# soldering_analog.net
KiCad netlist of a schematic drawn in Altium Designer
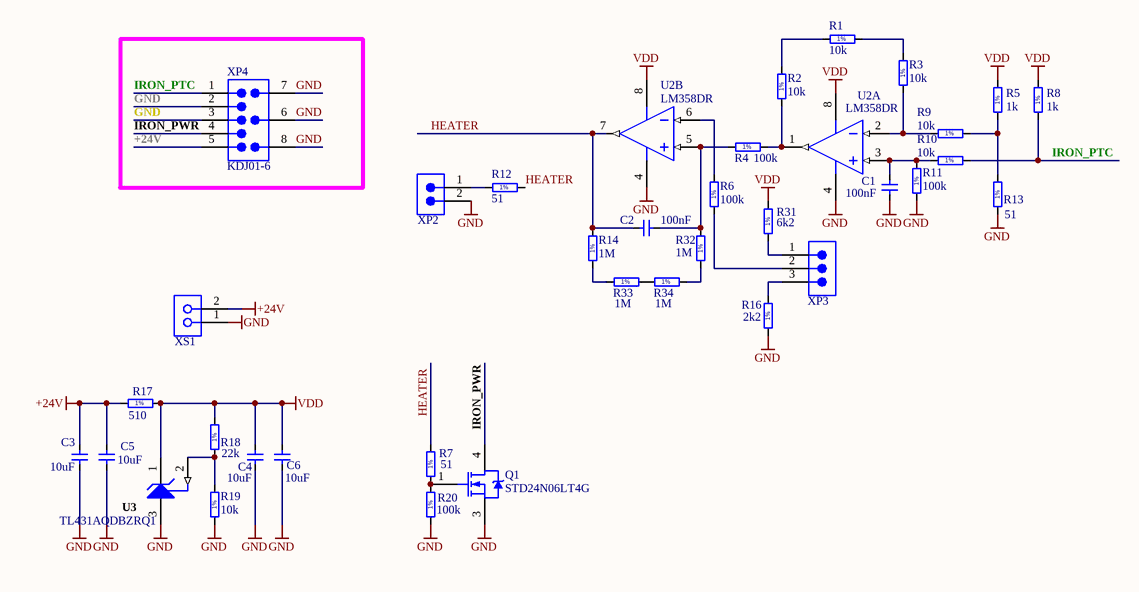
[diagram p0: soldering_analog.SchDoc]

(export (version "E")
  (design (tool "Eeschema 10.0.6"))
  (components
    (comp (ref "C1")
      (value "100nF")
      (footprint "CAP0805R")
      (fields
        (field (name "PART NUMBER") "CC0805_100NF_50V_10%_X7R")
        (field (name "VOLTAGE") "50V")
        (field (name "TOLERANCE") "±10%")
        (field (name "AUTHOR") "I. Kuznetsov")
      )
      (libsource (lib "Capacitor") (part "CAP_NON_POLAR"))
    )
    (comp (ref "C2")
      (value "100nF")
      (footprint "CAP0805R")
      (fields
        (field (name "PART NUMBER") "CC0805_100NF_50V_10%_X7R")
        (field (name "VOLTAGE") "50V")
        (field (name "TOLERANCE") "±10%")
        (field (name "AUTHOR") "I. Kuznetsov")
      )
      (libsource (lib "Capacitor") (part "CAP_NON_POLAR"))
    )
    (comp (ref "C3")
      (value "10uF")
      (footprint "CAP1206R")
      (fields
        (field (name "PART NUMBER") "CC1206_10UF_25V_10%_X7R")
        (field (name "VOLTAGE") "25V")
        (field (name "TOLERANCE") "±10%")
        (field (name "AUTHOR") "I. Kuznetsov")
      )
      (libsource (lib "Capacitor") (part "CAP_NON_POLAR"))
    )
    (comp (ref "C4")
      (value "10uF")
      (footprint "CAP1206R")
      (fields
        (field (name "PART NUMBER") "CC1206_10UF_25V_10%_X7R")
        (field (name "VOLTAGE") "25V")
        (field (name "TOLERANCE") "±10%")
        (field (name "AUTHOR") "I. Kuznetsov")
      )
      (libsource (lib "Capacitor") (part "CAP_NON_POLAR"))
    )
    (comp (ref "C5")
      (value "10uF")
      (footprint "CAP1206R")
      (fields
        (field (name "PART NUMBER") "CC1206_10UF_25V_10%_X7R")
        (field (name "VOLTAGE") "25V")
        (field (name "TOLERANCE") "±10%")
        (field (name "AUTHOR") "I. Kuznetsov")
      )
      (libsource (lib "Capacitor") (part "CAP_NON_POLAR"))
    )
    (comp (ref "C6")
      (value "10uF")
      (footprint "CAP1206R")
      (fields
        (field (name "PART NUMBER") "CC1206_10UF_25V_10%_X7R")
        (field (name "VOLTAGE") "25V")
        (field (name "TOLERANCE") "±10%")
        (field (name "AUTHOR") "I. Kuznetsov")
      )
      (libsource (lib "Capacitor") (part "CAP_NON_POLAR"))
    )
    (comp (ref "Q1")
      (value "STD24N06LT4G")
      (footprint "ONSC-DPAK-3-369C-01_V")
      (description "Power MOSFET, 24 A, 60 V, Logic Level, N-Channel, 3-Pin DPAK, Pb-Free, Tape and Reel")
      (fields (field (name "MANUFACTURER") "On Semiconductor"))
      (libsource (lib "Altium Content Vault") (part "ONSC-NMOS-G1S3D4-3_C"))
    )
    (comp (ref "R1")
      (value "10k")
      (footprint "RES0805R")
      (fields
        (field (name "PART NUMBER") "R0805_10K_1%_0.125W_100PPM")
        (field (name "POWER") "0.125W")
        (field (name "TOLERANCE") "±1%")
        (field (name "AUTHOR") "CERN DEM JLC")
      )
      (libsource (lib "Resistor") (part "Resistor - 1%"))
    )
    (comp (ref "R2")
      (value "10k")
      (footprint "RES0805R")
      (fields
        (field (name "PART NUMBER") "R0805_10K_1%_0.125W_100PPM")
        (field (name "POWER") "0.125W")
        (field (name "TOLERANCE") "±1%")
        (field (name "AUTHOR") "CERN DEM JLC")
      )
      (libsource (lib "Resistor") (part "Resistor - 1%"))
    )
    (comp (ref "R3")
      (value "10k")
      (footprint "RES0805R")
      (fields
        (field (name "PART NUMBER") "R0805_10K_1%_0.125W_100PPM")
        (field (name "POWER") "0.125W")
        (field (name "TOLERANCE") "±1%")
        (field (name "AUTHOR") "CERN DEM JLC")
      )
      (libsource (lib "Resistor") (part "Resistor - 1%"))
    )
    (comp (ref "R4")
      (value "100k")
      (footprint "RES0805R")
      (fields
        (field (name "PART NUMBER") "R0805_100K_1%_0.125W_100PPM")
        (field (name "POWER") "0.125W")
        (field (name "TOLERANCE") "±1%")
        (field (name "AUTHOR") "CERN DEM JLC")
      )
      (libsource (lib "Resistor") (part "Resistor - 1%"))
    )
    (comp (ref "R5")
      (value "1k")
      (footprint "RES0805R")
      (fields
        (field (name "PART NUMBER") "R0805_1K_1%_0.125W_100PPM")
        (field (name "POWER") "0.125W")
        (field (name "TOLERANCE") "±1%")
        (field (name "AUTHOR") "CERN DEM JLC")
      )
      (libsource (lib "Resistor") (part "Resistor - 1%"))
    )
    (comp (ref "R6")
      (value "100k")
      (footprint "RES0805R")
      (fields
        (field (name "PART NUMBER") "R0805_100K_1%_0.125W_100PPM")
        (field (name "POWER") "0.125W")
        (field (name "TOLERANCE") "±1%")
        (field (name "AUTHOR") "CERN DEM JLC")
      )
      (libsource (lib "Resistor") (part "Resistor - 1%"))
    )
    (comp (ref "R7")
      (value "51")
      (footprint "RES0805R")
      (fields
        (field (name "PART NUMBER") "R0805_51R_1%_0.125W_100PPM")
        (field (name "POWER") "0.125W")
        (field (name "TOLERANCE") "±1%")
        (field (name "AUTHOR") "CERN DEM JLC")
      )
      (libsource (lib "Resistor") (part "Resistor - 1%"))
    )
    (comp (ref "R8")
      (value "1k")
      (footprint "RES0805R")
      (fields
        (field (name "PART NUMBER") "R0805_1K_1%_0.125W_100PPM")
        (field (name "POWER") "0.125W")
        (field (name "TOLERANCE") "±1%")
        (field (name "AUTHOR") "CERN DEM JLC")
      )
      (libsource (lib "Resistor") (part "Resistor - 1%"))
    )
    (comp (ref "R9")
      (value "10k")
      (footprint "RES0805R")
      (fields
        (field (name "PART NUMBER") "R0805_10K_1%_0.125W_100PPM")
        (field (name "POWER") "0.125W")
        (field (name "TOLERANCE") "±1%")
        (field (name "AUTHOR") "CERN DEM JLC")
      )
      (libsource (lib "Resistor") (part "Resistor - 1%"))
    )
    (comp (ref "R10")
      (value "10k")
      (footprint "RES0805R")
      (fields
        (field (name "PART NUMBER") "R0805_10K_1%_0.125W_100PPM")
        (field (name "POWER") "0.125W")
        (field (name "TOLERANCE") "±1%")
        (field (name "AUTHOR") "CERN DEM JLC")
      )
      (libsource (lib "Resistor") (part "Resistor - 1%"))
    )
    (comp (ref "R11")
      (value "100k")
      (footprint "RES0805R")
      (fields
        (field (name "PART NUMBER") "R0805_100K_1%_0.125W_100PPM")
        (field (name "POWER") "0.125W")
        (field (name "TOLERANCE") "±1%")
        (field (name "AUTHOR") "CERN DEM JLC")
      )
      (libsource (lib "Resistor") (part "Resistor - 1%"))
    )
    (comp (ref "R12")
      (value "51")
      (footprint "RES0805R")
      (fields
        (field (name "PART NUMBER") "R0805_51R_1%_0.125W_100PPM")
        (field (name "POWER") "0.125W")
        (field (name "TOLERANCE") "±1%")
        (field (name "AUTHOR") "CERN DEM JLC")
      )
      (libsource (lib "Resistor") (part "Resistor - 1%"))
    )
    (comp (ref "R13")
      (value "51")
      (footprint "RES0805R")
      (fields
        (field (name "PART NUMBER") "R0805_51R_1%_0.125W_100PPM")
        (field (name "POWER") "0.125W")
        (field (name "TOLERANCE") "±1%")
        (field (name "AUTHOR") "CERN DEM JLC")
      )
      (libsource (lib "Resistor") (part "Resistor - 1%"))
    )
    (comp (ref "R14")
      (value "1M")
      (footprint "RES0805R")
      (fields
        (field (name "PART NUMBER") "R0805_1M_1%_0.125W_100PPM")
        (field (name "POWER") "0.125W")
        (field (name "TOLERANCE") "±1%")
        (field (name "AUTHOR") "CERN DEM JLC")
      )
      (libsource (lib "Resistor") (part "Resistor - 1%"))
    )
    (comp (ref "R16")
      (value "2k2")
      (footprint "RES0805R")
      (fields
        (field (name "PART NUMBER") "R0805_2K2_1%_0.125W_100PPM")
        (field (name "POWER") "0.125W")
        (field (name "TOLERANCE") "±1%")
        (field (name "AUTHOR") "CERN DEM JLC")
      )
      (libsource (lib "Resistor") (part "Resistor - 1%"))
    )
    (comp (ref "R17")
      (value "510")
      (footprint "RES0805R")
      (fields
        (field (name "PART NUMBER") "R0805_510R_1%_0.125W_100PPM")
        (field (name "POWER") "0.125W")
        (field (name "TOLERANCE") "±1%")
        (field (name "AUTHOR") "CERN DEM JLC")
      )
      (libsource (lib "Resistor") (part "Resistor - 1%"))
    )
    (comp (ref "R18")
      (value "22k")
      (footprint "RES0805R")
      (fields
        (field (name "PART NUMBER") "R0805_22K_1%_0.125W_100PPM")
        (field (name "POWER") "0.125W")
        (field (name "TOLERANCE") "±1%")
        (field (name "AUTHOR") "CERN DEM JLC")
      )
      (libsource (lib "Resistor") (part "Resistor - 1%"))
    )
    (comp (ref "R19")
      (value "10k")
      (footprint "RES0805R")
      (fields
        (field (name "PART NUMBER") "R0805_10K_1%_0.125W_100PPM")
        (field (name "POWER") "0.125W")
        (field (name "TOLERANCE") "±1%")
        (field (name "AUTHOR") "CERN DEM JLC")
      )
      (libsource (lib "Resistor") (part "Resistor - 1%"))
    )
    (comp (ref "R20")
      (value "100k")
      (footprint "RES0805R")
      (fields
        (field (name "PART NUMBER") "R0805_100K_1%_0.125W_100PPM")
        (field (name "POWER") "0.125W")
        (field (name "TOLERANCE") "±1%")
        (field (name "AUTHOR") "CERN DEM JLC")
      )
      (libsource (lib "Resistor") (part "Resistor - 1%"))
    )
    (comp (ref "R31")
      (value "6k2")
      (footprint "RES0805R")
      (fields
        (field (name "PART NUMBER") "R0805_6K2_1%_0.125W_100PPM")
        (field (name "POWER") "0.125W")
        (field (name "TOLERANCE") "±1%")
        (field (name "AUTHOR") "CERN DEM JLC")
      )
      (libsource (lib "Resistor") (part "Resistor - 1%"))
    )
    (comp (ref "R32")
      (value "1M")
      (footprint "RES0805R")
      (fields
        (field (name "PART NUMBER") "R0805_1M_1%_0.125W_100PPM")
        (field (name "POWER") "0.125W")
        (field (name "TOLERANCE") "±1%")
        (field (name "AUTHOR") "CERN DEM JLC")
      )
      (libsource (lib "Resistor") (part "Resistor - 1%"))
    )
    (comp (ref "R33")
      (value "1M")
      (footprint "RES0805R")
      (fields
        (field (name "PART NUMBER") "R0805_1M_1%_0.125W_100PPM")
        (field (name "POWER") "0.125W")
        (field (name "TOLERANCE") "±1%")
        (field (name "AUTHOR") "CERN DEM JLC")
      )
      (libsource (lib "Resistor") (part "Resistor - 1%"))
    )
    (comp (ref "R34")
      (value "1M")
      (footprint "RES0805R")
      (fields
        (field (name "PART NUMBER") "R0805_1M_1%_0.125W_100PPM")
        (field (name "POWER") "0.125W")
        (field (name "TOLERANCE") "±1%")
        (field (name "AUTHOR") "CERN DEM JLC")
      )
      (libsource (lib "Resistor") (part "Resistor - 1%"))
    )
    (comp (ref "U2")
      (value "LM358DR")
      (footprint "D0008A_L")
      (libsource (lib "Altium Content Vault") (part "TI-LM358-8"))
    )
    (comp (ref "U3")
      (value "TL431AQDBZRQ1")
      (footprint "DBZ0003A_M")
      (fields (field (name "MANUFACTURER") "Texas Instruments"))
      (libsource (lib "Altium Content Vault") (part "TI-TL431A-Q1DBZ3"))
    )
    (comp (ref "XP2")
      (value "PLS-02R")
      (footprint "PLS-02R")
      (libsource (lib "Connector") (part "CN_02P_1W"))
    )
    (comp (ref "XP3")
      (value "PLS-03R")
      (footprint "PLS-03R")
      (libsource (lib "Connector") (part "CN_03P_1W"))
    )
    (comp (ref "XP4") (value "KDJ01-6") (footprint "KDJ01-6") (libsource (lib "Connector") (part "KDJ01-6")))
    (comp (ref "XS1")
      (value "306-021-12")
      (footprint "306-021-12")
      (libsource (lib "Connector") (part "CN_02S_1W"))
    )
  )
  (nets
    (net (code "1") (name "+24V") (class "Default")
      (node (ref "C3") (pin "2") (pinfunction "2_2") (pintype "passive"))
      (node (ref "C5") (pin "2") (pinfunction "2_2") (pintype "passive"))
      (node (ref "R17") (pin "1") (pinfunction "1_1") (pintype "passive"))
      (node (ref "XP4") (pin "5") (pinfunction "5_5") (pintype "passive"))
      (node (ref "XS1") (pin "2") (pinfunction "2_2") (pintype "passive"))
    )
    (net (code "2") (name "/HEATER") (class "Default")
      (node (ref "C2") (pin "1") (pinfunction "1_1") (pintype "passive"))
      (node (ref "R12") (pin "2") (pinfunction "2_2") (pintype "passive"))
      (node (ref "R14") (pin "2") (pinfunction "2_2") (pintype "passive"))
      (node (ref "R7") (pin "2") (pinfunction "2_2") (pintype "passive"))
      (node (ref "U2") (pin "7") (pinfunction "2OUT_7") (pintype "output"))
    )
    (net (code "3") (name "/IRON_PTC") (class "Default")
      (node (ref "R10") (pin "2") (pinfunction "2_2") (pintype "passive"))
      (node (ref "R8") (pin "1") (pinfunction "1_1") (pintype "passive"))
      (node (ref "XP4") (pin "1") (pinfunction "1_1") (pintype "passive"))
    )
    (net (code "4") (name "/IRON_PWR") (class "Default")
      (node (ref "Q1") (pin "4") (pinfunction "D_4") (pintype "passive"))
      (node (ref "XP4") (pin "4") (pinfunction "4_4") (pintype "passive"))
    )
    (net (code "5") (name "GND") (class "Default")
      (node (ref "C1") (pin "1") (pinfunction "1_1") (pintype "passive"))
      (node (ref "C3") (pin "1") (pinfunction "1_1") (pintype "passive"))
      (node (ref "C4") (pin "1") (pinfunction "1_1") (pintype "passive"))
      (node (ref "C5") (pin "1") (pinfunction "1_1") (pintype "passive"))
      (node (ref "C6") (pin "1") (pinfunction "1_1") (pintype "passive"))
      (node (ref "Q1") (pin "3") (pinfunction "S_3") (pintype "passive"))
      (node (ref "R11") (pin "1") (pinfunction "1_1") (pintype "passive"))
      (node (ref "R13") (pin "1") (pinfunction "1_1") (pintype "passive"))
      (node (ref "R16") (pin "1") (pinfunction "1_1") (pintype "passive"))
      (node (ref "R19") (pin "1") (pinfunction "1_1") (pintype "passive"))
      (node (ref "R20") (pin "1") (pinfunction "1_1") (pintype "passive"))
      (node (ref "U2") (pin "4") (pinfunction "GND_4") (pintype "power_in"))
      (node (ref "U3") (pin "3") (pinfunction "ANODE_3") (pintype "power_in"))
      (node (ref "XP2") (pin "2") (pinfunction "2_2") (pintype "passive"))
      (node (ref "XP4") (pin "2") (pinfunction "2_2") (pintype "passive"))
      (node (ref "XP4") (pin "3") (pinfunction "3_3") (pintype "passive"))
      (node (ref "XP4") (pin "6") (pinfunction "6_6") (pintype "passive"))
      (node (ref "XP4") (pin "7") (pinfunction "7_7") (pintype "passive"))
      (node (ref "XP4") (pin "8") (pinfunction "8_8") (pintype "passive"))
      (node (ref "XS1") (pin "1") (pinfunction "1_1") (pintype "passive"))
    )
    (net (code "6") (name "Net-(Q1-G)") (class "Default")
      (node (ref "Q1") (pin "1") (pinfunction "G_1") (pintype "passive"))
      (node (ref "R20") (pin "2") (pinfunction "2_2") (pintype "passive"))
      (node (ref "R7") (pin "1") (pinfunction "1_1") (pintype "passive"))
    )
    (net (code "7") (name "Net-(R1-Pad1)") (class "Default")
      (node (ref "R1") (pin "1") (pinfunction "1_1") (pintype "passive"))
      (node (ref "R2") (pin "2") (pinfunction "2_2") (pintype "passive"))
    )
    (net (code "8") (name "Net-(R1-Pad2)") (class "Default")
      (node (ref "R1") (pin "2") (pinfunction "2_2") (pintype "passive"))
      (node (ref "R3") (pin "2") (pinfunction "2_2") (pintype "passive"))
    )
    (net (code "9") (name "Net-(R6-Pad1)") (class "Default")
      (node (ref "R6") (pin "1") (pinfunction "1_1") (pintype "passive"))
      (node (ref "XP3") (pin "2") (pinfunction "2_2") (pintype "passive"))
    )
    (net (code "10") (name "Net-(R12-Pad1)") (class "Default")
      (node (ref "R12") (pin "1") (pinfunction "1_1") (pintype "passive"))
      (node (ref "XP2") (pin "1") (pinfunction "1_1") (pintype "passive"))
    )
    (net (code "11") (name "Net-(R13-Pad2)") (class "Default")
      (node (ref "R13") (pin "2") (pinfunction "2_2") (pintype "passive"))
      (node (ref "R5") (pin "1") (pinfunction "1_1") (pintype "passive"))
      (node (ref "R9") (pin "2") (pinfunction "2_2") (pintype "passive"))
    )
    (net (code "12") (name "Net-(R14-Pad1)") (class "Default")
      (node (ref "R14") (pin "1") (pinfunction "1_1") (pintype "passive"))
      (node (ref "R33") (pin "1") (pinfunction "1_1") (pintype "passive"))
    )
    (net (code "13") (name "Net-(R16-Pad2)") (class "Default")
      (node (ref "R16") (pin "2") (pinfunction "2_2") (pintype "passive"))
      (node (ref "XP3") (pin "3") (pinfunction "3_3") (pintype "passive"))
    )
    (net (code "14") (name "Net-(R31-Pad1)") (class "Default")
      (node (ref "R31") (pin "1") (pinfunction "1_1") (pintype "passive"))
      (node (ref "XP3") (pin "1") (pinfunction "1_1") (pintype "passive"))
    )
    (net (code "15") (name "Net-(R32-Pad1)") (class "Default")
      (node (ref "R32") (pin "1") (pinfunction "1_1") (pintype "passive"))
      (node (ref "R34") (pin "2") (pinfunction "2_2") (pintype "passive"))
    )
    (net (code "16") (name "Net-(R33-Pad2)") (class "Default")
      (node (ref "R33") (pin "2") (pinfunction "2_2") (pintype "passive"))
      (node (ref "R34") (pin "1") (pinfunction "1_1") (pintype "passive"))
    )
    (net (code "17") (name "Net-(U2A-1IN+)") (class "Default")
      (node (ref "C1") (pin "2") (pinfunction "2_2") (pintype "passive"))
      (node (ref "R10") (pin "1") (pinfunction "1_1") (pintype "passive"))
      (node (ref "R11") (pin "2") (pinfunction "2_2") (pintype "passive"))
      (node (ref "U2") (pin "3") (pinfunction "1IN+_3") (pintype "input"))
    )
    (net (code "18") (name "Net-(U2A-1IN-)") (class "Default")
      (node (ref "R3") (pin "1") (pinfunction "1_1") (pintype "passive"))
      (node (ref "R9") (pin "1") (pinfunction "1_1") (pintype "passive"))
      (node (ref "U2") (pin "2") (pinfunction "1IN-_2") (pintype "input"))
    )
    (net (code "19") (name "Net-(U2A-1OUT)") (class "Default")
      (node (ref "R2") (pin "1") (pinfunction "1_1") (pintype "passive"))
      (node (ref "R4") (pin "2") (pinfunction "2_2") (pintype "passive"))
      (node (ref "U2") (pin "1") (pinfunction "1OUT_1") (pintype "output"))
    )
    (net (code "20") (name "Net-(U2B-2IN+)") (class "Default")
      (node (ref "C2") (pin "2") (pinfunction "2_2") (pintype "passive"))
      (node (ref "R32") (pin "2") (pinfunction "2_2") (pintype "passive"))
      (node (ref "R4") (pin "1") (pinfunction "1_1") (pintype "passive"))
      (node (ref "U2") (pin "5") (pinfunction "2IN+_5") (pintype "input"))
    )
    (net (code "21") (name "Net-(U2B-2IN-)") (class "Default")
      (node (ref "R6") (pin "2") (pinfunction "2_2") (pintype "passive"))
      (node (ref "U2") (pin "6") (pinfunction "2IN-_6") (pintype "input"))
    )
    (net (code "22") (name "Net-(U3-REF)") (class "Default")
      (node (ref "R18") (pin "1") (pinfunction "1_1") (pintype "passive"))
      (node (ref "R19") (pin "2") (pinfunction "2_2") (pintype "passive"))
      (node (ref "U3") (pin "2") (pinfunction "REF_2") (pintype "input"))
    )
    (net (code "23") (name "VDD") (class "Default")
      (node (ref "C4") (pin "2") (pinfunction "2_2") (pintype "passive"))
      (node (ref "C6") (pin "2") (pinfunction "2_2") (pintype "passive"))
      (node (ref "R17") (pin "2") (pinfunction "2_2") (pintype "passive"))
      (node (ref "R18") (pin "2") (pinfunction "2_2") (pintype "passive"))
      (node (ref "R31") (pin "2") (pinfunction "2_2") (pintype "passive"))
      (node (ref "R5") (pin "2") (pinfunction "2_2") (pintype "passive"))
      (node (ref "R8") (pin "2") (pinfunction "2_2") (pintype "passive"))
      (node (ref "U2") (pin "8") (pinfunction "VCC_8") (pintype "power_in"))
      (node (ref "U3") (pin "1") (pinfunction "CATHODE_1") (pintype "passive"))
    )
  )
)
